# keycontrol_MCU.net
KiCad netlist of a schematic drawn in Altium Designer
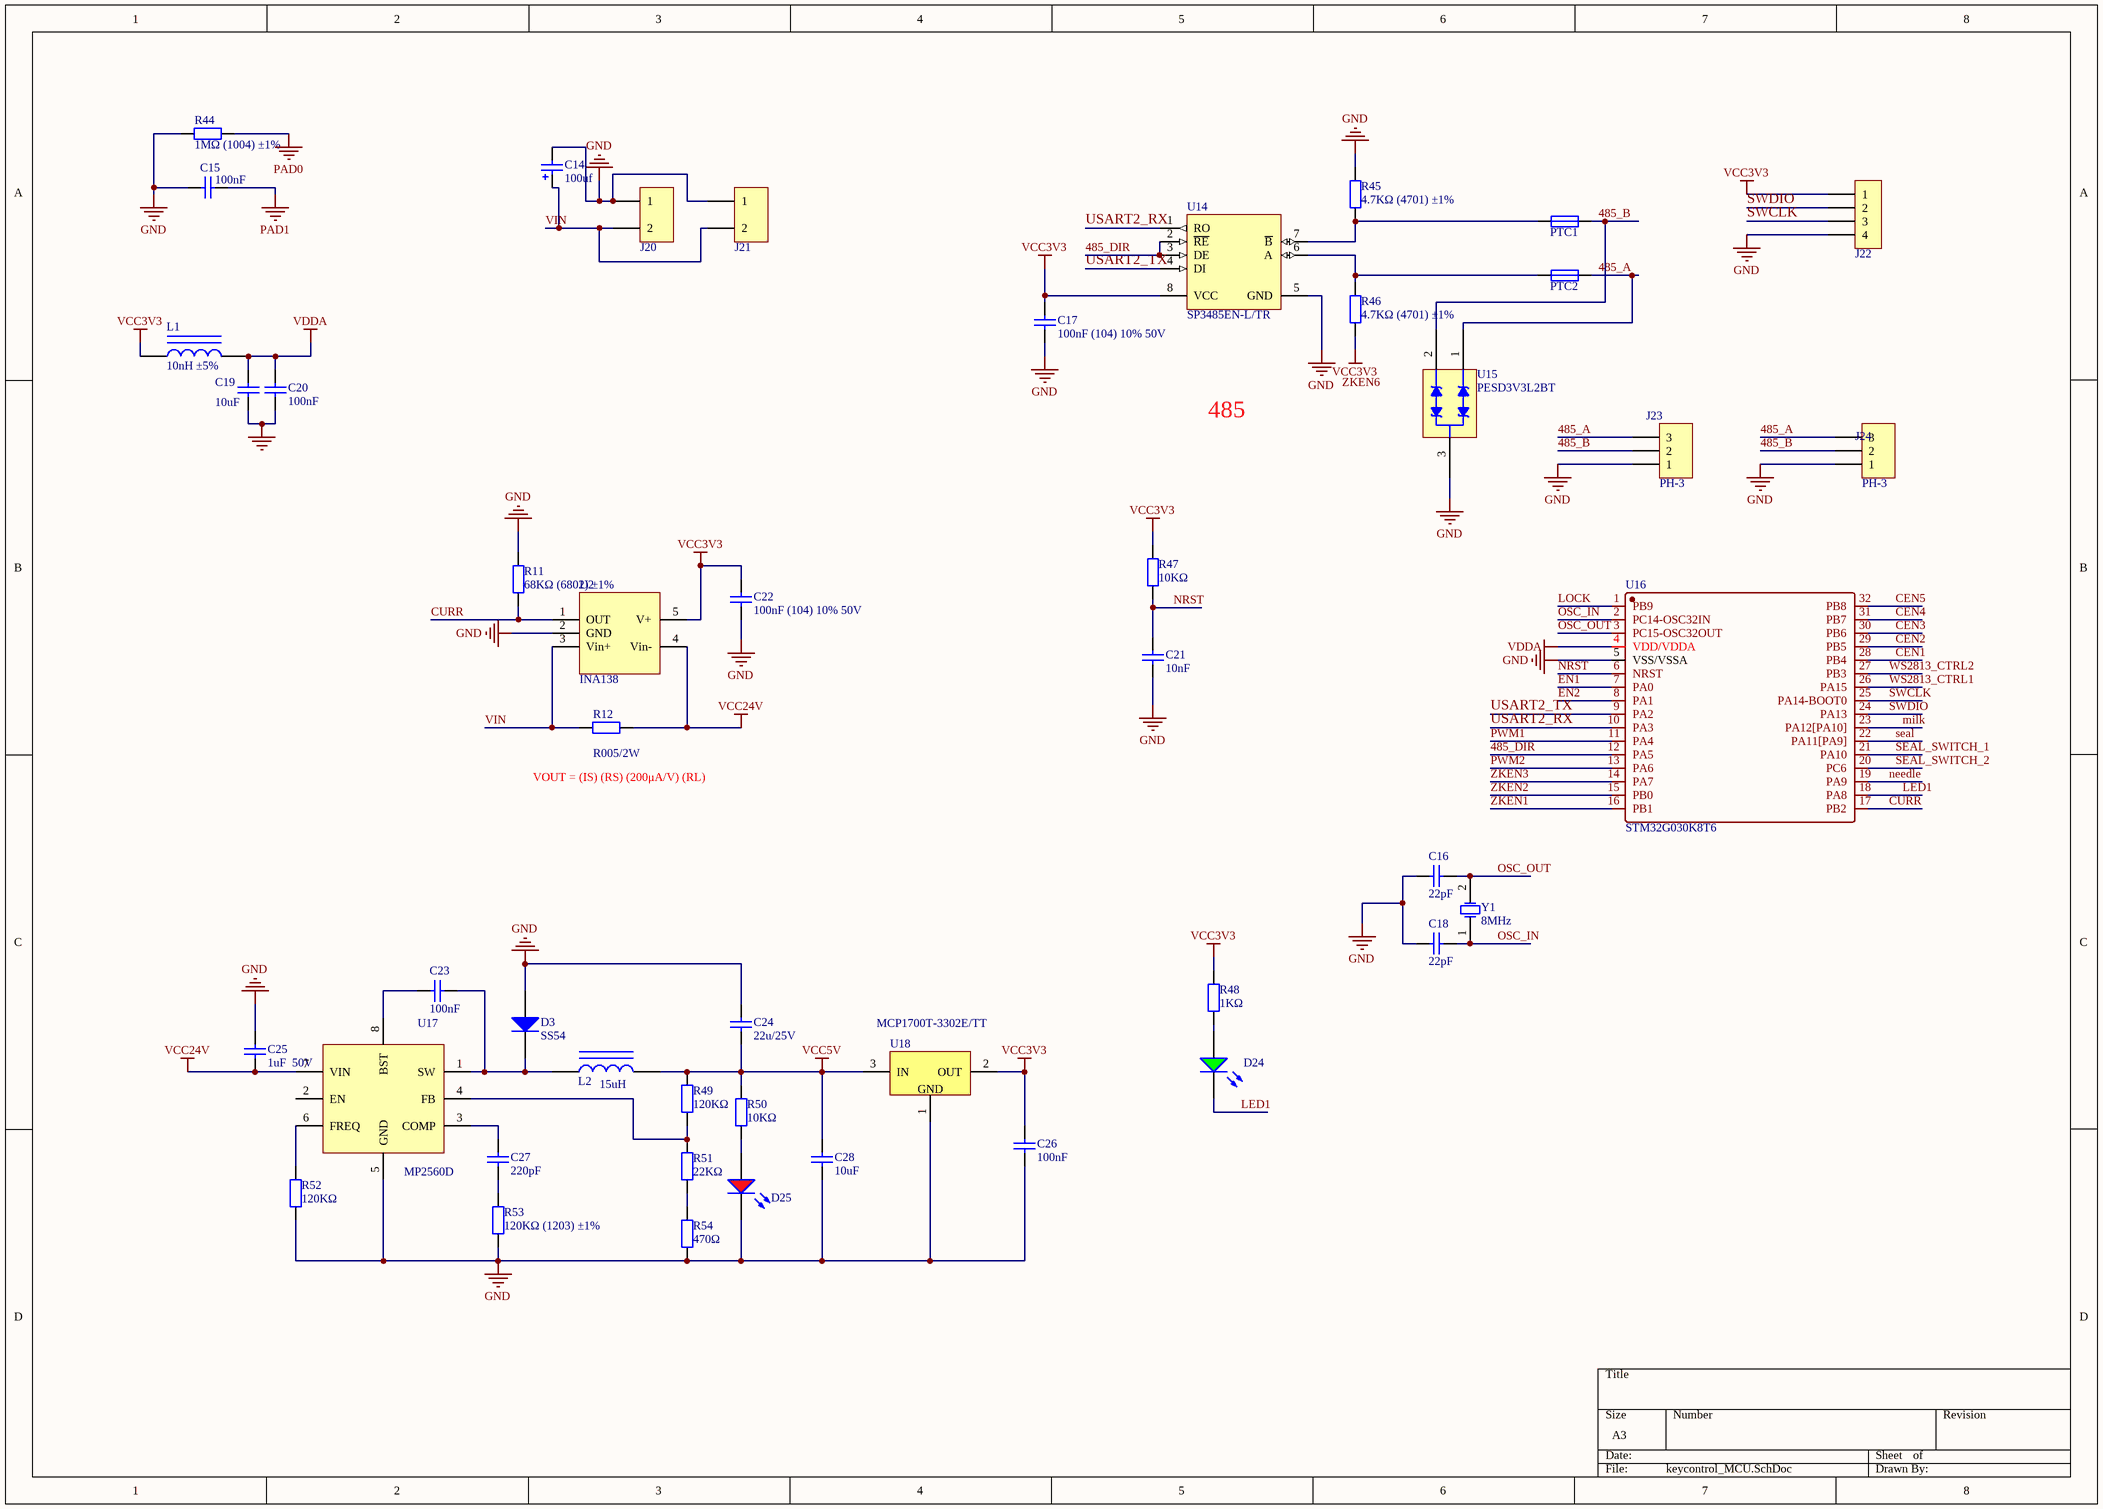
[diagram p0: keycontrol_MCU.SchDoc]

(export (version "E")
  (design (tool "Eeschema 10.0.6"))
  (components
    (comp (ref "C14") (value "100uf") (footprint "E_6.3*5.4") (libsource (lib "我的集成库") (part "C")))
    (comp (ref "C15")
      (value "100nF")
      (footprint "0603_C")
      (description "贴片电容")
      (libsource (lib "AD封装2018.9.19Miscellaneous Devices LC") (part "0603 100nF (104) 10% 50V"))
    )
    (comp (ref "C16")
      (value "22pF")
      (footprint "0603_C")
      (description "贴片电容")
      (libsource (lib "Cap") (part "0603 22pF (220) 5% 50V"))
    )
    (comp (ref "C17")
      (value "100nF (104) 10% 50V")
      (footprint "0603_C")
      (description "贴片电容")
      (libsource (lib "AD封装2018.9.19Miscellaneous Devices LC") (part "0603 100nF (104) 10% 50V"))
    )
    (comp (ref "C18")
      (value "22pF")
      (footprint "0603_C")
      (description "贴片电容")
      (libsource (lib "Cap") (part "0603 22pF (220) 5% 50V"))
    )
    (comp (ref "C19")
      (value "10uF")
      (footprint "0603_C")
      (description "贴片电容")
      (libsource (lib "AD封装2018.9.19Miscellaneous Devices LC") (part "0603 10uF (106) 10% 10V"))
    )
    (comp (ref "C20")
      (value "100nF")
      (footprint "0603_C")
      (description "贴片电容")
      (libsource (lib "AD封装2018.9.19Miscellaneous Devices LC") (part "0603 100nF (104) 10% 50V"))
    )
    (comp (ref "C21")
      (value "10nF")
      (footprint "0603_C")
      (description "贴片电容")
      (libsource (lib "AD封装2018.9.19Miscellaneous Devices LC") (part "0603 10nF (103) 10% 50V"))
    )
    (comp (ref "C22")
      (value "100nF (104) 10% 50V")
      (footprint "0603_C")
      (description "贴片电容")
      (libsource (lib "AD封装2018.9.19Miscellaneous Devices LC") (part "0603 100nF (104) 10% 50V"))
    )
    (comp (ref "C23")
      (value "100nF")
      (footprint "0603_C")
      (description "贴片电容")
      (libsource (lib "AD封装2018.9.19Miscellaneous Devices LC") (part "0603 100nF (104) 10% 50V"))
    )
    (comp (ref "C24")
      (value "22u/25V")
      (footprint "1206_C")
      (description "贴片电容")
      (libsource (lib "AD封装2018.9.19Miscellaneous Devices LC") (part "1206 220pF (221) 10% 50V"))
    )
    (comp (ref "C25")
      (value "1uF  50V")
      (footprint "0603_C")
      (description "贴片电容")
      (libsource (lib "AD封装2018.9.19Miscellaneous Devices LC") (part "0603 1uF (105) 10% 50V"))
    )
    (comp (ref "C26")
      (value "100nF")
      (footprint "0603_C")
      (description "贴片电容")
      (libsource (lib "AD封装2018.9.19Miscellaneous Devices LC") (part "0603 100nF (104) 10% 50V"))
    )
    (comp (ref "C27")
      (value "220pF")
      (footprint "0603_C")
      (description "贴片电容")
      (libsource (lib "AD封装2018.9.19Miscellaneous Devices LC") (part "0603 220pF (221) 10% 50V"))
    )
    (comp (ref "C28")
      (value "10uF")
      (footprint "0603_C")
      (description "贴片电容")
      (libsource (lib "AD封装2018.9.19Miscellaneous Devices LC") (part "0603 10uF (106) 10% 10V"))
    )
    (comp (ref "D3")
      (value "SS54")
      (footprint "SMA(DO-214AC)_S1")
      (description "二极管")
      (libsource (lib "AD封装2018.9.19Miscellaneous Devices LC") (part "SMA(DO-214AC) SS54"))
    )
    (comp (ref "D24")
      (value "绿灯 0603")
      (footprint "0603_LED_S1")
      (description "发光二极管")
      (libsource (lib "AD封装2018.9.19Miscellaneous Devices LC") (part "0603 绿灯"))
    )
    (comp (ref "D25")
      (value "红灯 0603")
      (footprint "0603_LED_S1")
      (description "发光二极管")
      (libsource (lib "AD封装2018.9.19Miscellaneous Devices LC") (part "0603 红灯"))
    )
    (comp (ref "J20") (value "MOTOR") (footprint "5557_a") (libsource (lib "我的集成库") (part "header2")))
    (comp (ref "J21") (value "MOTOR") (footprint "5557_a") (libsource (lib "我的集成库") (part "header2")))
    (comp (ref "J22") (value "header4") (footprint "xh-4") (libsource (lib "我的集成库") (part "header4")))
    (comp (ref "J23") (value "PH-3") (footprint "ph3-2.0") (libsource (lib "我的集成库") (part "XH-3")))
    (comp (ref "J24") (value "PH-3") (footprint "ph3-2.0") (libsource (lib "我的集成库") (part "XH-3")))
    (comp (ref "L1")
      (value "10nH ±5%")
      (footprint "0603_L")
      (description "贴片电感")
      (libsource (lib "AD封装2018.9.19Miscellaneous Devices LC") (part "0603 10nH 5%"))
    )
    (comp (ref "L2")
      (value "15uH")
      (footprint "LSMD,3.3*6.6*3mm")
      (description "YSPI0730-150M")
      (libsource (lib "我的集成库") (part "induct"))
    )
    (comp (ref "PTC1") (value "PTC") (footprint "PTC") (libsource (lib "我的集成库") (part "PTC")))
    (comp (ref "PTC2") (value "PTC") (footprint "PTC") (libsource (lib "我的集成库") (part "PTC")))
    (comp (ref "R11")
      (value "68KΩ (6802) ±1%")
      (footprint "0603_R")
      (description "贴片电阻")
      (libsource (lib "AD封装2018.9.19Miscellaneous Devices LC") (part "0603 68KΩ (6802) 1%"))
    )
    (comp (ref "R12") (value "R005/2W") (footprint "2512") (libsource (lib "我的集成库") (part "RES")))
    (comp (ref "R44")
      (value "1MΩ (1004) ±1%")
      (footprint "0603_R")
      (description "贴片电阻")
      (libsource (lib "AD封装2018.9.19Miscellaneous Devices LC") (part "0603 1MΩ (1004) 1%"))
    )
    (comp (ref "R45")
      (value "4.7KΩ (4701) ±1%")
      (footprint "0603_R")
      (description "贴片电阻")
      (libsource (lib "AD封装2018.9.19Miscellaneous Devices LC") (part "0603 4.7KΩ (4701) 1%"))
    )
    (comp (ref "R46")
      (value "4.7KΩ (4701) ±1%")
      (footprint "0603_R")
      (description "贴片电阻")
      (libsource (lib "AD封装2018.9.19Miscellaneous Devices LC") (part "0603 4.7KΩ (4701) 1%"))
    )
    (comp (ref "R47")
      (value "10KΩ")
      (footprint "0603_R")
      (description "贴片电阻")
      (libsource (lib "AD封装2018.9.19Miscellaneous Devices LC") (part "0603 10KΩ (1002) 1%"))
    )
    (comp (ref "R48")
      (value "1KΩ")
      (footprint "0603_R")
      (description "贴片电阻")
      (libsource (lib "AD封装2018.9.19Miscellaneous Devices LC") (part "0603 1KΩ (1001) 1%"))
    )
    (comp (ref "R49")
      (value "120KΩ")
      (footprint "0603_R")
      (description "贴片电阻")
      (libsource (lib "AD封装2018.9.19Miscellaneous Devices LC") (part "0603 120KΩ (1203) 1%"))
    )
    (comp (ref "R50")
      (value "10KΩ")
      (footprint "0603_R")
      (description "贴片电阻")
      (libsource (lib "AD封装2018.9.19Miscellaneous Devices LC") (part "0603 10KΩ (1002) 1%"))
    )
    (comp (ref "R51")
      (value "22KΩ")
      (footprint "0603_R")
      (description "贴片电阻")
      (libsource (lib "AD封装2018.9.19Miscellaneous Devices LC") (part "0603 22KΩ (2202) 1%"))
    )
    (comp (ref "R52")
      (value "120KΩ")
      (footprint "0603_R")
      (description "贴片电阻")
      (libsource (lib "") (part "0603 120KΩ (1203) 1%_1"))
    )
    (comp (ref "R53")
      (value "120KΩ (1203) ±1%")
      (footprint "0603_R")
      (description "贴片电阻")
      (libsource (lib "AD封装2018.9.19Miscellaneous Devices LC") (part "0603 120KΩ (1203) 1%"))
    )
    (comp (ref "R54")
      (value "470Ω")
      (footprint "0603_R")
      (description "贴片电阻")
      (libsource (lib "AD封装2018.9.19Miscellaneous Devices LC") (part "0603 470Ω (4700) 1%"))
    )
    (comp (ref "U2")
      (value "INA138")
      (footprint "SOT-23-5")
      (description "SOT-23-5")
      (libsource (lib "我的集成库") (part "INA138"))
    )
    (comp (ref "U14")
      (value "SP3485EN-L/TR")
      (footprint "SOIC-8_150mil")
      (description "RS-485/RS-422")
      (libsource (lib "IC") (part "SP3485EN-L/TR_[C8963]"))
    )
    (comp (ref "U15")
      (value "PESD3V3L2BT")
      (footprint "SOT-23(SOT-23-3)")
      (description "TVS")
      (libsource (lib "AD封装2018.9.19Miscellaneous Devices LC") (part "PSM712-LF-T7_[C32677]"))
    )
    (comp (ref "U16")
      (value "STM32G030K8T6")
      (footprint "LQFP-32")
      (description "MCU")
      (libsource (lib "我的集成库") (part "STM32G030K8T6"))
    )
    (comp (ref "U17")
      (value "MP2560D")
      (footprint "SOP-8_150mil")
      (description "MP2560D_SOIC-8_EP_150mil")
      (libsource (lib "我的集成库") (part "MP2560D"))
    )
    (comp (ref "U18")
      (value "MCP1700T-3302E/TT")
      (footprint "SOT-23-3")
      (description "https://item.szlcsc.com/40034.html LDO 3.3V")
      (libsource (lib "我的集成库") (part "MCP1700T-3302E/TT LDO 3.3V"))
    )
    (comp (ref "Y1")
      (value "8MHz")
      (footprint "SMD-5032_2P")
      (description "贴片晶振")
      (libsource (lib "CrystalOscillator") (part "SMD-5032_2P 8MHz 20ppm 20pF"))
    )
  )
  (nets
    (net (code "1") (name "/485_A") (class "Default")
      (node (ref "J23") (pin "3") (pinfunction "3_3") (pintype "passive"))
      (node (ref "J24") (pin "3") (pinfunction "3_3") (pintype "passive"))
      (node (ref "PTC2") (pin "2") (pinfunction "2_2") (pintype "passive"))
      (node (ref "U15") (pin "1") (pinfunction "1_1") (pintype "passive"))
    )
    (net (code "2") (name "/485_B") (class "Default")
      (node (ref "J23") (pin "2") (pinfunction "2_2") (pintype "passive"))
      (node (ref "J24") (pin "2") (pinfunction "2_2") (pintype "passive"))
      (node (ref "PTC1") (pin "2") (pinfunction "2_2") (pintype "passive"))
      (node (ref "U15") (pin "2") (pinfunction "2_2") (pintype "passive"))
    )
    (net (code "3") (name "/485_DIR") (class "Default")
      (node (ref "U14") (pin "2") (pinfunction "~{RE}_2") (pintype "input"))
      (node (ref "U14") (pin "3") (pinfunction "DE_3") (pintype "input"))
      (node (ref "U16") (pin "12") (pinfunction "PA5_12") (pintype "passive"))
    )
    (net (code "4") (name "/CEN1") (class "Default")
      (node (ref "U16") (pin "28") (pinfunction "PB4_28") (pintype "passive"))
    )
    (net (code "5") (name "/CEN2") (class "Default")
      (node (ref "U16") (pin "29") (pinfunction "PB5_29") (pintype "passive"))
    )
    (net (code "6") (name "/CEN3") (class "Default")
      (node (ref "U16") (pin "30") (pinfunction "PB6_30") (pintype "passive"))
    )
    (net (code "7") (name "/CEN4") (class "Default")
      (node (ref "U16") (pin "31") (pinfunction "PB7_31") (pintype "passive"))
    )
    (net (code "8") (name "/CEN5") (class "Default")
      (node (ref "U16") (pin "32") (pinfunction "PB8_32") (pintype "passive"))
    )
    (net (code "9") (name "/CURR") (class "Default")
      (node (ref "R11") (pin "1") (pinfunction "1_1") (pintype "passive"))
      (node (ref "U16") (pin "17") (pinfunction "PB2_17") (pintype "passive"))
      (node (ref "U2") (pin "1") (pinfunction "OUT_1") (pintype "passive"))
    )
    (net (code "10") (name "/EN1") (class "Default")
      (node (ref "U16") (pin "7") (pinfunction "PA0_7") (pintype "passive"))
    )
    (net (code "11") (name "/EN2") (class "Default")
      (node (ref "U16") (pin "8") (pinfunction "PA1_8") (pintype "passive"))
    )
    (net (code "12") (name "/LED1") (class "Default")
      (node (ref "D24") (pin "K") (pinfunction "K_K") (pintype "passive"))
      (node (ref "U16") (pin "18") (pinfunction "PA8_18") (pintype "passive"))
    )
    (net (code "13") (name "/LOCK") (class "Default")
      (node (ref "U16") (pin "1") (pinfunction "PB9_1") (pintype "passive"))
    )
    (net (code "14") (name "/NRST") (class "Default")
      (node (ref "C21") (pin "2") (pinfunction "2_2") (pintype "passive"))
      (node (ref "R47") (pin "1") (pinfunction "1_1") (pintype "passive"))
      (node (ref "U16") (pin "6") (pinfunction "NRST_6") (pintype "passive"))
    )
    (net (code "15") (name "/OSC_IN") (class "Default")
      (node (ref "C18") (pin "2") (pinfunction "2_2") (pintype "passive"))
      (node (ref "U16") (pin "2") (pinfunction "PC14-OSC32IN_2") (pintype "passive"))
      (node (ref "Y1") (pin "1") (pinfunction "OSC1_1") (pintype "passive"))
    )
    (net (code "16") (name "/OSC_OUT") (class "Default")
      (node (ref "C16") (pin "2") (pinfunction "2_2") (pintype "passive"))
      (node (ref "U16") (pin "3") (pinfunction "PC15-OSC32OUT_3") (pintype "passive"))
      (node (ref "Y1") (pin "2") (pinfunction "OSC2_2") (pintype "passive"))
    )
    (net (code "17") (name "/PWM1") (class "Default")
      (node (ref "U16") (pin "11") (pinfunction "PA4_11") (pintype "passive"))
    )
    (net (code "18") (name "/PWM2") (class "Default")
      (node (ref "U16") (pin "13") (pinfunction "PA6_13") (pintype "passive"))
    )
    (net (code "19") (name "/SEAL_SWITCH_1") (class "Default")
      (node (ref "U16") (pin "21") (pinfunction "PA10_21") (pintype "passive"))
    )
    (net (code "20") (name "/SEAL_SWITCH_2") (class "Default")
      (node (ref "U16") (pin "20") (pinfunction "PC6_20") (pintype "passive"))
    )
    (net (code "21") (name "/SWCLK") (class "Default")
      (node (ref "J22") (pin "3") (pinfunction "3_3") (pintype "passive"))
      (node (ref "U16") (pin "25") (pinfunction "PA14-BOOT0_25") (pintype "passive"))
    )
    (net (code "22") (name "/SWDIO") (class "Default")
      (node (ref "J22") (pin "2") (pinfunction "2_2") (pintype "passive"))
      (node (ref "U16") (pin "24") (pinfunction "PA13_24") (pintype "passive"))
    )
    (net (code "23") (name "/USART2_RX") (class "Default")
      (node (ref "U14") (pin "1") (pinfunction "RO_1") (pintype "output"))
      (node (ref "U16") (pin "10") (pinfunction "PA3_10") (pintype "passive"))
    )
    (net (code "24") (name "/USART2_TX") (class "Default")
      (node (ref "U14") (pin "4") (pinfunction "DI_4") (pintype "input"))
      (node (ref "U16") (pin "9") (pinfunction "PA2_9") (pintype "passive"))
    )
    (net (code "25") (name "/VIN") (class "Default")
      (node (ref "C14") (pin "1") (pinfunction "1_1") (pintype "passive"))
      (node (ref "J20") (pin "2") (pinfunction "2_2") (pintype "passive"))
      (node (ref "J21") (pin "2") (pinfunction "2_2") (pintype "passive"))
      (node (ref "R12") (pin "1") (pinfunction "1_1") (pintype "passive"))
      (node (ref "U2") (pin "3") (pinfunction "Vin+_3") (pintype "passive"))
    )
    (net (code "26") (name "/WS2813_CTRL1") (class "Default")
      (node (ref "U16") (pin "26") (pinfunction "PA15_26") (pintype "passive"))
    )
    (net (code "27") (name "/WS2813_CTRL2") (class "Default")
      (node (ref "U16") (pin "27") (pinfunction "PB3_27") (pintype "passive"))
    )
    (net (code "28") (name "/ZKEN1") (class "Default")
      (node (ref "U16") (pin "16") (pinfunction "PB1_16") (pintype "passive"))
    )
    (net (code "29") (name "/ZKEN2") (class "Default")
      (node (ref "U16") (pin "15") (pinfunction "PB0_15") (pintype "passive"))
    )
    (net (code "30") (name "/ZKEN3") (class "Default")
      (node (ref "U16") (pin "14") (pinfunction "PA7_14") (pintype "passive"))
    )
    (net (code "32") (name "/milk") (class "Default")
      (node (ref "U16") (pin "23") (pinfunction "PA12[PA10]_23") (pintype "passive"))
    )
    (net (code "33") (name "/needle") (class "Default")
      (node (ref "U16") (pin "19") (pinfunction "PA9_19") (pintype "passive"))
    )
    (net (code "34") (name "/seal") (class "Default")
      (node (ref "U16") (pin "22") (pinfunction "PA11[PA9]_22") (pintype "passive"))
    )
    (net (code "35") (name "GND") (class "Default")
      (node (ref "C14") (pin "2") (pinfunction "2_2") (pintype "passive"))
      (node (ref "C15") (pin "1") (pinfunction "1_1") (pintype "passive"))
      (node (ref "C16") (pin "1") (pinfunction "1_1") (pintype "passive"))
      (node (ref "C17") (pin "1") (pinfunction "1_1") (pintype "passive"))
      (node (ref "C18") (pin "1") (pinfunction "1_1") (pintype "passive"))
      (node (ref "C19") (pin "1") (pinfunction "1_1") (pintype "passive"))
      (node (ref "C20") (pin "1") (pinfunction "1_1") (pintype "passive"))
      (node (ref "C21") (pin "1") (pinfunction "1_1") (pintype "passive"))
      (node (ref "C22") (pin "1") (pinfunction "1_1") (pintype "passive"))
      (node (ref "C24") (pin "2") (pinfunction "2_2") (pintype "passive"))
      (node (ref "C25") (pin "2") (pinfunction "2_2") (pintype "passive"))
      (node (ref "C26") (pin "1") (pinfunction "1_1") (pintype "passive"))
      (node (ref "C28") (pin "1") (pinfunction "1_1") (pintype "passive"))
      (node (ref "D25") (pin "K") (pinfunction "K_K") (pintype "passive"))
      (node (ref "D3") (pin "1") (pinfunction "A_1") (pintype "passive"))
      (node (ref "J20") (pin "1") (pinfunction "1_1") (pintype "passive"))
      (node (ref "J21") (pin "1") (pinfunction "1_1") (pintype "passive"))
      (node (ref "J22") (pin "4") (pinfunction "4_4") (pintype "passive"))
      (node (ref "J23") (pin "1") (pinfunction "1_1") (pintype "passive"))
      (node (ref "J24") (pin "1") (pinfunction "1_1") (pintype "passive"))
      (node (ref "R11") (pin "2") (pinfunction "2_2") (pintype "passive"))
      (node (ref "R44") (pin "1") (pinfunction "1_1") (pintype "passive"))
      (node (ref "R45") (pin "2") (pinfunction "2_2") (pintype "passive"))
      (node (ref "R52") (pin "1") (pinfunction "1_1") (pintype "passive"))
      (node (ref "R53") (pin "2") (pinfunction "2_2") (pintype "passive"))
      (node (ref "R54") (pin "1") (pinfunction "1_1") (pintype "passive"))
      (node (ref "U14") (pin "5") (pinfunction "GND_5") (pintype "power_in"))
      (node (ref "U15") (pin "3") (pinfunction "3_3") (pintype "passive"))
      (node (ref "U16") (pin "5") (pinfunction "VSS/VSSA_5") (pintype "passive"))
      (node (ref "U17") (pin "5") (pinfunction "GND_5") (pintype "passive"))
      (node (ref "U18") (pin "1") (pintype "passive"))
      (node (ref "U2") (pin "2") (pinfunction "GND_2") (pintype "passive"))
    )
    (net (code "36") (name "Net-(C27-Pad1)") (class "Default")
      (node (ref "C27") (pin "1") (pinfunction "1_1") (pintype "passive"))
      (node (ref "R53") (pin "1") (pinfunction "1_1") (pintype "passive"))
    )
    (net (code "37") (name "Net-(D3-K)") (class "Default")
      (node (ref "C23") (pin "2") (pinfunction "2_2") (pintype "passive"))
      (node (ref "D3") (pin "2") (pinfunction "K_2") (pintype "passive"))
      (node (ref "L2") (pin "1") (pinfunction "1_1") (pintype "passive"))
      (node (ref "U17") (pin "1") (pinfunction "SW_1") (pintype "passive"))
    )
    (net (code "38") (name "Net-(D24-PadA)") (class "Default")
      (node (ref "D24") (pin "A") (pinfunction "A_A") (pintype "passive"))
      (node (ref "R48") (pin "1") (pinfunction "1_1") (pintype "passive"))
    )
    (net (code "39") (name "Net-(D25-PadA)") (class "Default")
      (node (ref "D25") (pin "A") (pinfunction "A_A") (pintype "passive"))
      (node (ref "R50") (pin "1") (pinfunction "1_1") (pintype "passive"))
    )
    (net (code "40") (name "Net-(R51-Pad1)") (class "Default")
      (node (ref "R51") (pin "1") (pinfunction "1_1") (pintype "passive"))
      (node (ref "R54") (pin "2") (pinfunction "2_2") (pintype "passive"))
    )
    (net (code "41") (name "Net-(U14-A)") (class "Default")
      (node (ref "PTC2") (pin "1") (pinfunction "1_1") (pintype "passive"))
      (node (ref "R46") (pin "2") (pinfunction "2_2") (pintype "passive"))
      (node (ref "U14") (pin "6") (pinfunction "A_6") (pintype "bidirectional"))
    )
    (net (code "42") (name "Net-(U14-~{B})") (class "Default")
      (node (ref "PTC1") (pin "1") (pinfunction "1_1") (pintype "passive"))
      (node (ref "R45") (pin "1") (pinfunction "1_1") (pintype "passive"))
      (node (ref "U14") (pin "7") (pinfunction "~{B}_7") (pintype "bidirectional"))
    )
    (net (code "43") (name "Net-(U17-BST)") (class "Default")
      (node (ref "C23") (pin "1") (pinfunction "1_1") (pintype "passive"))
      (node (ref "U17") (pin "8") (pinfunction "BST_8") (pintype "passive"))
    )
    (net (code "44") (name "Net-(U17-COMP)") (class "Default")
      (node (ref "C27") (pin "2") (pinfunction "2_2") (pintype "passive"))
      (node (ref "U17") (pin "3") (pinfunction "COMP_3") (pintype "passive"))
    )
    (net (code "45") (name "Net-(U17-FB)") (class "Default")
      (node (ref "R49") (pin "2") (pinfunction "2_2") (pintype "passive"))
      (node (ref "R51") (pin "2") (pinfunction "2_2") (pintype "passive"))
      (node (ref "U17") (pin "4") (pinfunction "FB_4") (pintype "passive"))
    )
    (net (code "46") (name "Net-(U17-FREQ)") (class "Default")
      (node (ref "R52") (pin "2") (pinfunction "2_2") (pintype "passive"))
      (node (ref "U17") (pin "6") (pinfunction "FREQ_6") (pintype "passive"))
    )
    (net (code "47") (name "PAD0") (class "Default")
      (node (ref "R44") (pin "2") (pinfunction "2_2") (pintype "passive"))
    )
    (net (code "48") (name "PAD1") (class "Default")
      (node (ref "C15") (pin "2") (pinfunction "2_2") (pintype "passive"))
    )
    (net (code "49") (name "VCC3V3") (class "Default")
      (node (ref "C17") (pin "2") (pinfunction "2_2") (pintype "passive"))
      (node (ref "C22") (pin "2") (pinfunction "2_2") (pintype "passive"))
      (node (ref "C26") (pin "2") (pinfunction "2_2") (pintype "passive"))
      (node (ref "J22") (pin "1") (pinfunction "1_1") (pintype "passive"))
      (node (ref "L1") (pin "1") (pinfunction "1_1") (pintype "passive"))
      (node (ref "R46") (pin "1") (pinfunction "1_1") (pintype "passive"))
      (node (ref "R47") (pin "2") (pinfunction "2_2") (pintype "passive"))
      (node (ref "R48") (pin "2") (pinfunction "2_2") (pintype "passive"))
      (node (ref "U14") (pin "8") (pinfunction "VCC_8") (pintype "power_in"))
      (node (ref "U18") (pin "2") (pinfunction "OUT_2") (pintype "passive"))
      (node (ref "U2") (pin "5") (pinfunction "V+_5") (pintype "passive"))
    )
    (net (code "50") (name "VCC5V") (class "Default")
      (node (ref "C24") (pin "1") (pinfunction "1_1") (pintype "passive"))
      (node (ref "C28") (pin "2") (pinfunction "2_2") (pintype "passive"))
      (node (ref "L2") (pin "2") (pinfunction "2_2") (pintype "passive"))
      (node (ref "R49") (pin "1") (pinfunction "1_1") (pintype "passive"))
      (node (ref "R50") (pin "2") (pinfunction "2_2") (pintype "passive"))
      (node (ref "U18") (pin "3") (pinfunction "IN_3") (pintype "passive"))
    )
    (net (code "51") (name "VCC24V") (class "Default")
      (node (ref "C25") (pin "1") (pinfunction "1_1") (pintype "passive"))
      (node (ref "R12") (pin "2") (pinfunction "2_2") (pintype "passive"))
      (node (ref "U17") (pin "7") (pinfunction "VIN_7") (pintype "passive"))
      (node (ref "U2") (pin "4") (pinfunction "Vin-_4") (pintype "passive"))
    )
    (net (code "52") (name "VDDA") (class "Default")
      (node (ref "C19") (pin "2") (pinfunction "2_2") (pintype "passive"))
      (node (ref "C20") (pin "2") (pinfunction "2_2") (pintype "passive"))
      (node (ref "L1") (pin "2") (pinfunction "2_2") (pintype "passive"))
      (node (ref "U16") (pin "4") (pinfunction "VDD/VDDA_4") (pintype "passive"))
    )
    (net (code "53") (name "unconnected-(U17-EN-Pad2)") (class "Default")
      (node (ref "U17") (pin "2") (pinfunction "EN_2") (pintype "passive"))
    )
  )
)
